# USB_Experiment_Board.net
KiCad netlist of a schematic drawn in EAGLE
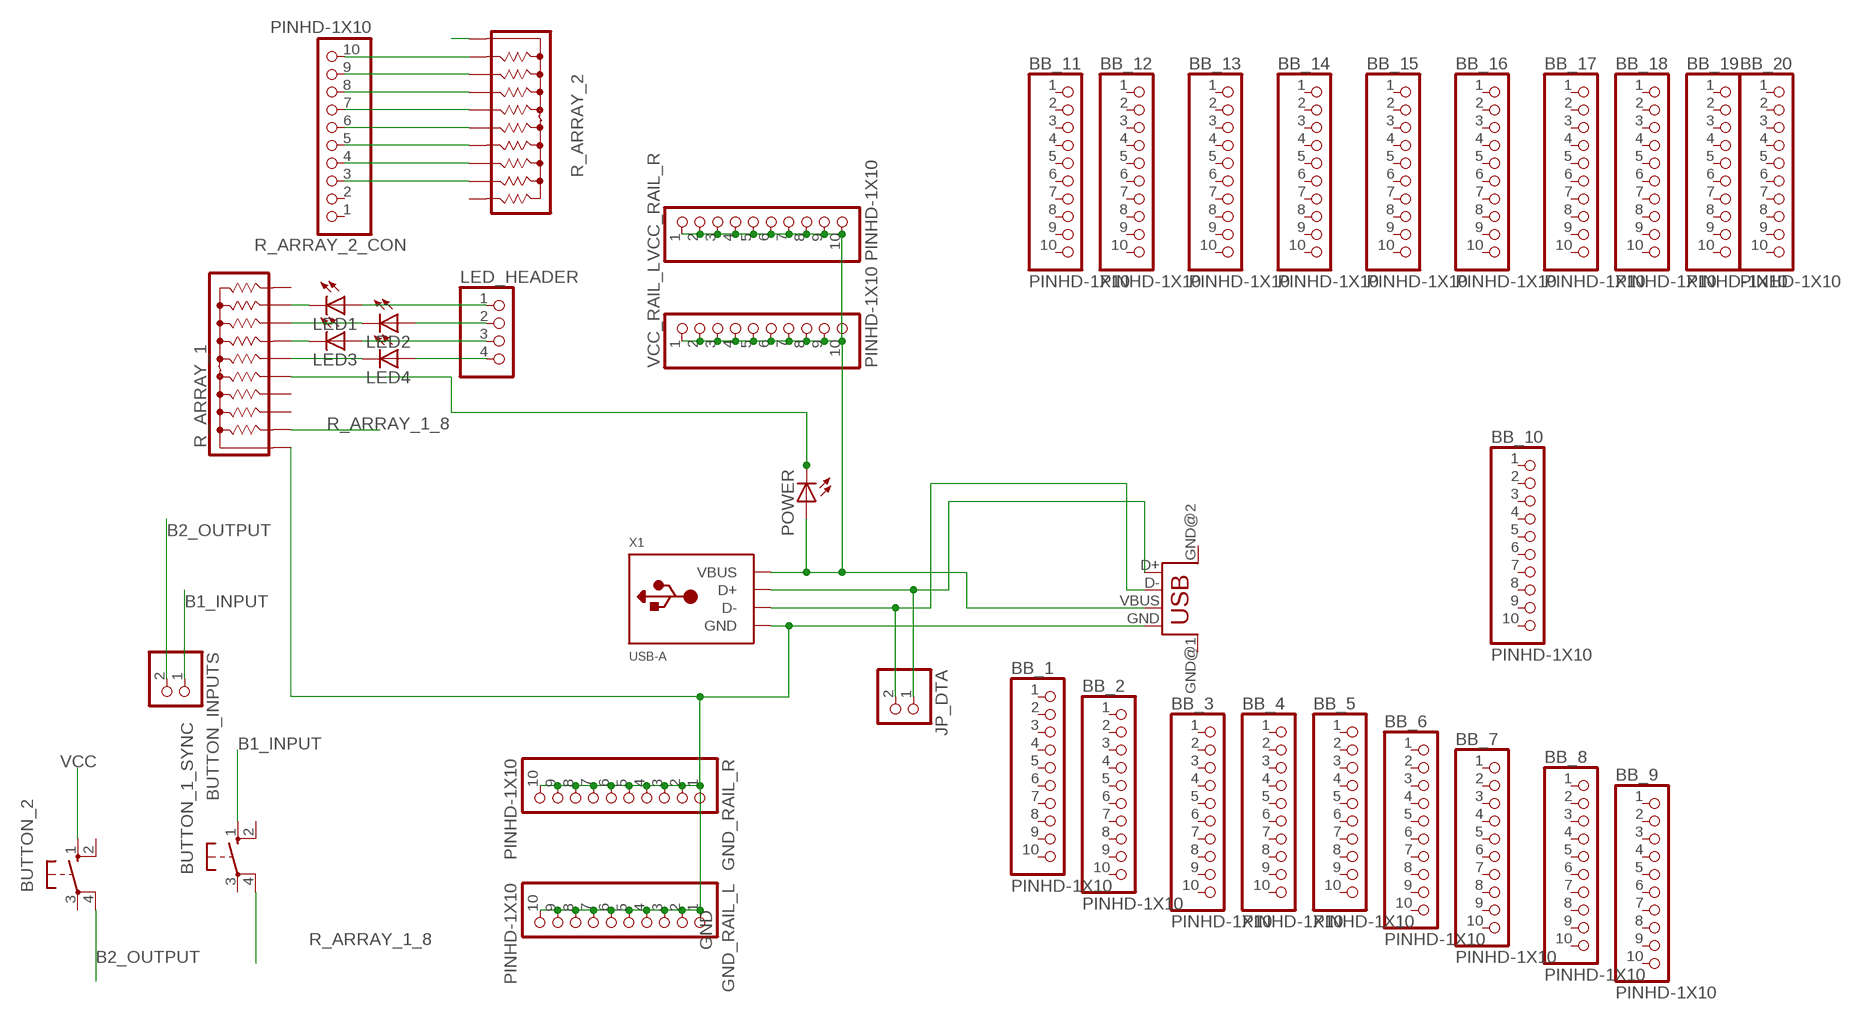
[diagram p0: schematic, sheet 1]

(export (version "E")
  (design (tool "Eeschema 10.0.6"))
  (components
    (comp (ref "BB_1")
      (value "PINHD-1X10")
      (footprint "eagle-import:1X10-BIG")
      (libsource (lib "eagle-import") (part "PINHD-1X10"))
    )
    (comp (ref "BB_2")
      (value "PINHD-1X10")
      (footprint "eagle-import:1X10-BIG")
      (libsource (lib "eagle-import") (part "PINHD-1X10"))
    )
    (comp (ref "BB_3")
      (value "PINHD-1X10")
      (footprint "eagle-import:1X10-BIG")
      (libsource (lib "eagle-import") (part "PINHD-1X10"))
    )
    (comp (ref "BB_4")
      (value "PINHD-1X10")
      (footprint "eagle-import:1X10-BIG")
      (libsource (lib "eagle-import") (part "PINHD-1X10"))
    )
    (comp (ref "BB_5")
      (value "PINHD-1X10")
      (footprint "eagle-import:1X10-BIG")
      (libsource (lib "eagle-import") (part "PINHD-1X10"))
    )
    (comp (ref "BB_6")
      (value "PINHD-1X10")
      (footprint "eagle-import:1X10-BIG")
      (libsource (lib "eagle-import") (part "PINHD-1X10"))
    )
    (comp (ref "BB_7")
      (value "PINHD-1X10")
      (footprint "eagle-import:1X10-BIG")
      (libsource (lib "eagle-import") (part "PINHD-1X10"))
    )
    (comp (ref "BB_8")
      (value "PINHD-1X10")
      (footprint "eagle-import:1X10-BIG")
      (libsource (lib "eagle-import") (part "PINHD-1X10"))
    )
    (comp (ref "BB_9")
      (value "PINHD-1X10")
      (footprint "eagle-import:1X10-BIG")
      (libsource (lib "eagle-import") (part "PINHD-1X10"))
    )
    (comp (ref "BB_10")
      (value "PINHD-1X10")
      (footprint "eagle-import:1X10-BIG")
      (libsource (lib "eagle-import") (part "PINHD-1X10"))
    )
    (comp (ref "BB_11")
      (value "PINHD-1X10")
      (footprint "eagle-import:1X10-BIG")
      (libsource (lib "eagle-import") (part "PINHD-1X10"))
    )
    (comp (ref "BB_12")
      (value "PINHD-1X10")
      (footprint "eagle-import:1X10-BIG")
      (libsource (lib "eagle-import") (part "PINHD-1X10"))
    )
    (comp (ref "BB_13")
      (value "PINHD-1X10")
      (footprint "eagle-import:1X10-BIG")
      (libsource (lib "eagle-import") (part "PINHD-1X10"))
    )
    (comp (ref "BB_14")
      (value "PINHD-1X10")
      (footprint "eagle-import:1X10-BIG")
      (libsource (lib "eagle-import") (part "PINHD-1X10"))
    )
    (comp (ref "BB_15")
      (value "PINHD-1X10")
      (footprint "eagle-import:1X10-BIG")
      (libsource (lib "eagle-import") (part "PINHD-1X10"))
    )
    (comp (ref "BB_16")
      (value "PINHD-1X10")
      (footprint "eagle-import:1X10-BIG")
      (libsource (lib "eagle-import") (part "PINHD-1X10"))
    )
    (comp (ref "BB_17")
      (value "PINHD-1X10")
      (footprint "eagle-import:1X10-BIG")
      (libsource (lib "eagle-import") (part "PINHD-1X10"))
    )
    (comp (ref "BB_18")
      (value "PINHD-1X10")
      (footprint "eagle-import:1X10-BIG")
      (libsource (lib "eagle-import") (part "PINHD-1X10"))
    )
    (comp (ref "BB_19")
      (value "PINHD-1X10")
      (footprint "eagle-import:1X10-BIG")
      (libsource (lib "eagle-import") (part "PINHD-1X10"))
    )
    (comp (ref "BB_20")
      (value "PINHD-1X10")
      (footprint "eagle-import:1X10-BIG")
      (libsource (lib "eagle-import") (part "PINHD-1X10"))
    )
    (comp (ref "BUTTON_1_SYNC")
      (value "10-XX")
      (footprint "eagle-import:B3F-10XX")
      (fields (field (name "MPN") "B3F-1000"))
      (libsource (lib "eagle-import") (part "10-XX"))
    )
    (comp (ref "BUTTON_2")
      (value "10-XX")
      (footprint "eagle-import:B3F-10XX")
      (fields (field (name "MPN") "B3F-1000"))
      (libsource (lib "eagle-import") (part "10-XX"))
    )
    (comp (ref "BUTTON_INPUTS")
      (value "PINHD-1X2")
      (footprint "eagle-import:1X02")
      (libsource (lib "eagle-import") (part "PINHD-1X2"))
    )
    (comp (ref "GND_RAIL_L")
      (value "PINHD-1X10")
      (footprint "eagle-import:1X10-BIG")
      (libsource (lib "eagle-import") (part "PINHD-1X10"))
    )
    (comp (ref "GND_RAIL_R")
      (value "PINHD-1X10")
      (footprint "eagle-import:1X10-BIG")
      (libsource (lib "eagle-import") (part "PINHD-1X10"))
    )
    (comp (ref "JP_DTA")
      (value "PINHD-1X2")
      (footprint "eagle-import:1X02")
      (libsource (lib "eagle-import") (part "PINHD-1X2"))
    )
    (comp (ref "LED1")
      (value "LEDSMT1206")
      (footprint "eagle-import:1206")
      (libsource (lib "eagle-import") (part "LEDSMT1206"))
    )
    (comp (ref "LED2")
      (value "LEDSMT1206")
      (footprint "eagle-import:1206")
      (libsource (lib "eagle-import") (part "LEDSMT1206"))
    )
    (comp (ref "LED3")
      (value "LEDSMT1206")
      (footprint "eagle-import:1206")
      (libsource (lib "eagle-import") (part "LEDSMT1206"))
    )
    (comp (ref "LED4")
      (value "LEDSMT1206")
      (footprint "eagle-import:1206")
      (libsource (lib "eagle-import") (part "LEDSMT1206"))
    )
    (comp (ref "LED_HEADER")
      (value "PINHD-1X4")
      (footprint "eagle-import:1X04")
      (libsource (lib "eagle-import") (part "PINHD-1X4"))
    )
    (comp (ref "POWER")
      (value "LEDSMT1206")
      (footprint "eagle-import:1206")
      (libsource (lib "eagle-import") (part "LEDSMT1206"))
    )
    (comp (ref "R_ARRAY_1")
      (value "4610X")
      (footprint "eagle-import:SIP10")
      (libsource (lib "eagle-import") (part "4610X"))
    )
    (comp (ref "R_ARRAY_2")
      (value "4610X")
      (footprint "eagle-import:SIP10")
      (libsource (lib "eagle-import") (part "4610X"))
    )
    (comp (ref "R_ARRAY_2_CON")
      (value "PINHD-1X10")
      (footprint "eagle-import:1X10-BIG")
      (libsource (lib "eagle-import") (part "PINHD-1X10"))
    )
    (comp (ref "U$1")
      (value "USB")
      (footprint "eagle-import:USB-FEMALE-A-PTH")
      (libsource (lib "eagle-import") (part "USB"))
    )
    (comp (ref "VCC_RAIL_L")
      (value "PINHD-1X10")
      (footprint "eagle-import:1X10-BIG")
      (libsource (lib "eagle-import") (part "PINHD-1X10"))
    )
    (comp (ref "VCC_RAIL_R")
      (value "PINHD-1X10")
      (footprint "eagle-import:1X10-BIG")
      (libsource (lib "eagle-import") (part "PINHD-1X10"))
    )
    (comp (ref "X1")
      (value "USB-A")
      (footprint "eagle-import:MOLEX_480371000")
      (libsource (lib "eagle-import") (part "USB-A"))
    )
  )
  (nets
    (net (code "1") (name "/B1_INPUT") (class "Default")
      (node (ref "BUTTON_1_SYNC") (pin "1") (pinfunction "S_1") (pintype "passive"))
      (node (ref "BUTTON_INPUTS") (pin "1") (pinfunction "1_1") (pintype "passive"))
    )
    (net (code "2") (name "/B2_OUTPUT") (class "Default")
      (node (ref "BUTTON_2") (pin "4") (pinfunction "P1_4") (pintype "passive"))
      (node (ref "BUTTON_INPUTS") (pin "2") (pinfunction "2_2") (pintype "passive"))
    )
    (net (code "3") (name "/GND") (class "Default")
      (node (ref "GND_RAIL_L") (pin "1") (pinfunction "1_1") (pintype "passive"))
      (node (ref "GND_RAIL_L") (pin "10") (pinfunction "10_10") (pintype "passive"))
      (node (ref "GND_RAIL_L") (pin "2") (pinfunction "2_2") (pintype "passive"))
      (node (ref "GND_RAIL_L") (pin "3") (pinfunction "3_3") (pintype "passive"))
      (node (ref "GND_RAIL_L") (pin "4") (pinfunction "4_4") (pintype "passive"))
      (node (ref "GND_RAIL_L") (pin "5") (pinfunction "5_5") (pintype "passive"))
      (node (ref "GND_RAIL_L") (pin "6") (pinfunction "6_6") (pintype "passive"))
      (node (ref "GND_RAIL_L") (pin "7") (pinfunction "7_7") (pintype "passive"))
      (node (ref "GND_RAIL_L") (pin "8") (pinfunction "8_8") (pintype "passive"))
      (node (ref "GND_RAIL_L") (pin "9") (pinfunction "9_9") (pintype "passive"))
      (node (ref "GND_RAIL_R") (pin "1") (pinfunction "1_1") (pintype "passive"))
      (node (ref "GND_RAIL_R") (pin "10") (pinfunction "10_10") (pintype "passive"))
      (node (ref "GND_RAIL_R") (pin "2") (pinfunction "2_2") (pintype "passive"))
      (node (ref "GND_RAIL_R") (pin "3") (pinfunction "3_3") (pintype "passive"))
      (node (ref "GND_RAIL_R") (pin "4") (pinfunction "4_4") (pintype "passive"))
      (node (ref "GND_RAIL_R") (pin "5") (pinfunction "5_5") (pintype "passive"))
      (node (ref "GND_RAIL_R") (pin "6") (pinfunction "6_6") (pintype "passive"))
      (node (ref "GND_RAIL_R") (pin "7") (pinfunction "7_7") (pintype "passive"))
      (node (ref "GND_RAIL_R") (pin "8") (pinfunction "8_8") (pintype "passive"))
      (node (ref "GND_RAIL_R") (pin "9") (pinfunction "9_9") (pintype "passive"))
      (node (ref "R_ARRAY_1") (pin "1") (pinfunction "1_1") (pintype "passive"))
      (node (ref "R_ARRAY_2") (pin "1") (pinfunction "1_1") (pintype "passive"))
      (node (ref "U$1") (pin "GND") (pinfunction "GND_GND") (pintype "bidirectional"))
      (node (ref "X1") (pin "4") (pinfunction "GND_4") (pintype "power_in"))
    )
    (net (code "4") (name "/R_ARRAY_1_8") (class "Default")
      (node (ref "BUTTON_1_SYNC") (pin "4") (pinfunction "P1_4") (pintype "passive"))
      (node (ref "R_ARRAY_1") (pin "2") (pinfunction "2_2") (pintype "passive"))
    )
    (net (code "5") (name "/VCC") (class "Default")
      (node (ref "BUTTON_2") (pin "1") (pinfunction "S_1") (pintype "passive"))
      (node (ref "POWER") (pin "A") (pinfunction "A_A") (pintype "passive"))
      (node (ref "U$1") (pin "VBUS") (pinfunction "VBUS_VBUS") (pintype "bidirectional"))
      (node (ref "VCC_RAIL_L") (pin "1") (pinfunction "1_1") (pintype "passive"))
      (node (ref "VCC_RAIL_L") (pin "10") (pinfunction "10_10") (pintype "passive"))
      (node (ref "VCC_RAIL_L") (pin "2") (pinfunction "2_2") (pintype "passive"))
      (node (ref "VCC_RAIL_L") (pin "3") (pinfunction "3_3") (pintype "passive"))
      (node (ref "VCC_RAIL_L") (pin "4") (pinfunction "4_4") (pintype "passive"))
      (node (ref "VCC_RAIL_L") (pin "5") (pinfunction "5_5") (pintype "passive"))
      (node (ref "VCC_RAIL_L") (pin "6") (pinfunction "6_6") (pintype "passive"))
      (node (ref "VCC_RAIL_L") (pin "7") (pinfunction "7_7") (pintype "passive"))
      (node (ref "VCC_RAIL_L") (pin "8") (pinfunction "8_8") (pintype "passive"))
      (node (ref "VCC_RAIL_L") (pin "9") (pinfunction "9_9") (pintype "passive"))
      (node (ref "VCC_RAIL_R") (pin "1") (pinfunction "1_1") (pintype "passive"))
      (node (ref "VCC_RAIL_R") (pin "10") (pinfunction "10_10") (pintype "passive"))
      (node (ref "VCC_RAIL_R") (pin "2") (pinfunction "2_2") (pintype "passive"))
      (node (ref "VCC_RAIL_R") (pin "3") (pinfunction "3_3") (pintype "passive"))
      (node (ref "VCC_RAIL_R") (pin "4") (pinfunction "4_4") (pintype "passive"))
      (node (ref "VCC_RAIL_R") (pin "5") (pinfunction "5_5") (pintype "passive"))
      (node (ref "VCC_RAIL_R") (pin "6") (pinfunction "6_6") (pintype "passive"))
      (node (ref "VCC_RAIL_R") (pin "7") (pinfunction "7_7") (pintype "passive"))
      (node (ref "VCC_RAIL_R") (pin "8") (pinfunction "8_8") (pintype "passive"))
      (node (ref "VCC_RAIL_R") (pin "9") (pinfunction "9_9") (pintype "passive"))
      (node (ref "X1") (pin "1") (pinfunction "VBUS_1") (pintype "power_in"))
    )
    (net (code "6") (name "Net-(LED1-PadA)") (class "Default")
      (node (ref "LED1") (pin "A") (pinfunction "A_A") (pintype "passive"))
      (node (ref "LED_HEADER") (pin "1") (pinfunction "1_1") (pintype "passive"))
    )
    (net (code "7") (name "Net-(LED1-PadC)") (class "Default")
      (node (ref "LED1") (pin "C") (pinfunction "C_C") (pintype "passive"))
      (node (ref "R_ARRAY_1") (pin "9") (pinfunction "9_9") (pintype "passive"))
    )
    (net (code "8") (name "Net-(LED2-PadA)") (class "Default")
      (node (ref "LED2") (pin "A") (pinfunction "A_A") (pintype "passive"))
      (node (ref "LED_HEADER") (pin "2") (pinfunction "2_2") (pintype "passive"))
    )
    (net (code "9") (name "Net-(LED2-PadC)") (class "Default")
      (node (ref "LED2") (pin "C") (pinfunction "C_C") (pintype "passive"))
      (node (ref "R_ARRAY_1") (pin "8") (pinfunction "8_8") (pintype "passive"))
    )
    (net (code "10") (name "Net-(LED3-PadA)") (class "Default")
      (node (ref "LED3") (pin "A") (pinfunction "A_A") (pintype "passive"))
      (node (ref "LED_HEADER") (pin "3") (pinfunction "3_3") (pintype "passive"))
    )
    (net (code "11") (name "Net-(LED3-PadC)") (class "Default")
      (node (ref "LED3") (pin "C") (pinfunction "C_C") (pintype "passive"))
      (node (ref "R_ARRAY_1") (pin "7") (pinfunction "7_7") (pintype "passive"))
    )
    (net (code "12") (name "Net-(LED4-PadA)") (class "Default")
      (node (ref "LED4") (pin "A") (pinfunction "A_A") (pintype "passive"))
      (node (ref "LED_HEADER") (pin "4") (pinfunction "4_4") (pintype "passive"))
    )
    (net (code "13") (name "Net-(LED4-PadC)") (class "Default")
      (node (ref "LED4") (pin "C") (pinfunction "C_C") (pintype "passive"))
      (node (ref "R_ARRAY_1") (pin "6") (pinfunction "6_6") (pintype "passive"))
    )
    (net (code "14") (name "Net-(POWER-PadC)") (class "Default")
      (node (ref "POWER") (pin "C") (pinfunction "C_C") (pintype "passive"))
      (node (ref "R_ARRAY_1") (pin "5") (pinfunction "5_5") (pintype "passive"))
    )
    (net (code "15") (name "Net-(R_ARRAY_2-Pad2)") (class "Default")
      (node (ref "R_ARRAY_2") (pin "2") (pinfunction "2_2") (pintype "passive"))
      (node (ref "R_ARRAY_2_CON") (pin "10") (pinfunction "10_10") (pintype "passive"))
    )
    (net (code "16") (name "Net-(R_ARRAY_2-Pad3)") (class "Default")
      (node (ref "R_ARRAY_2") (pin "3") (pinfunction "3_3") (pintype "passive"))
      (node (ref "R_ARRAY_2_CON") (pin "9") (pinfunction "9_9") (pintype "passive"))
    )
    (net (code "17") (name "Net-(R_ARRAY_2-Pad4)") (class "Default")
      (node (ref "R_ARRAY_2") (pin "4") (pinfunction "4_4") (pintype "passive"))
      (node (ref "R_ARRAY_2_CON") (pin "8") (pinfunction "8_8") (pintype "passive"))
    )
    (net (code "18") (name "Net-(R_ARRAY_2-Pad5)") (class "Default")
      (node (ref "R_ARRAY_2") (pin "5") (pinfunction "5_5") (pintype "passive"))
      (node (ref "R_ARRAY_2_CON") (pin "7") (pinfunction "7_7") (pintype "passive"))
    )
    (net (code "19") (name "Net-(R_ARRAY_2-Pad6)") (class "Default")
      (node (ref "R_ARRAY_2") (pin "6") (pinfunction "6_6") (pintype "passive"))
      (node (ref "R_ARRAY_2_CON") (pin "6") (pinfunction "6_6") (pintype "passive"))
    )
    (net (code "20") (name "Net-(R_ARRAY_2-Pad7)") (class "Default")
      (node (ref "R_ARRAY_2") (pin "7") (pinfunction "7_7") (pintype "passive"))
      (node (ref "R_ARRAY_2_CON") (pin "5") (pinfunction "5_5") (pintype "passive"))
    )
    (net (code "21") (name "Net-(R_ARRAY_2-Pad8)") (class "Default")
      (node (ref "R_ARRAY_2") (pin "8") (pinfunction "8_8") (pintype "passive"))
      (node (ref "R_ARRAY_2_CON") (pin "4") (pinfunction "4_4") (pintype "passive"))
    )
    (net (code "22") (name "Net-(R_ARRAY_2-Pad9)") (class "Default")
      (node (ref "R_ARRAY_2") (pin "9") (pinfunction "9_9") (pintype "passive"))
      (node (ref "R_ARRAY_2_CON") (pin "3") (pinfunction "3_3") (pintype "passive"))
    )
    (net (code "23") (name "Net-(X1-D+)") (class "Default")
      (node (ref "JP_DTA") (pin "1") (pinfunction "1_1") (pintype "passive"))
      (node (ref "U$1") (pin "D+") (pinfunction "D+_D+") (pintype "bidirectional"))
      (node (ref "X1") (pin "3") (pinfunction "D+_3") (pintype "bidirectional"))
    )
    (net (code "24") (name "Net-(X1-D-)") (class "Default")
      (node (ref "JP_DTA") (pin "2") (pinfunction "2_2") (pintype "passive"))
      (node (ref "U$1") (pin "D-") (pinfunction "D-_D-") (pintype "bidirectional"))
      (node (ref "X1") (pin "2") (pinfunction "D-_2") (pintype "bidirectional"))
    )
    (net (code "25") (name "unconnected-(BB_1-Pad1)") (class "Default")
      (node (ref "BB_1") (pin "1") (pinfunction "1_1") (pintype "passive"))
    )
    (net (code "26") (name "unconnected-(BB_1-Pad2)") (class "Default")
      (node (ref "BB_1") (pin "2") (pinfunction "2_2") (pintype "passive"))
    )
    (net (code "27") (name "unconnected-(BB_1-Pad3)") (class "Default")
      (node (ref "BB_1") (pin "3") (pinfunction "3_3") (pintype "passive"))
    )
    (net (code "28") (name "unconnected-(BB_1-Pad4)") (class "Default")
      (node (ref "BB_1") (pin "4") (pinfunction "4_4") (pintype "passive"))
    )
    (net (code "29") (name "unconnected-(BB_1-Pad5)") (class "Default")
      (node (ref "BB_1") (pin "5") (pinfunction "5_5") (pintype "passive"))
    )
    (net (code "30") (name "unconnected-(BB_1-Pad6)") (class "Default")
      (node (ref "BB_1") (pin "6") (pinfunction "6_6") (pintype "passive"))
    )
    (net (code "31") (name "unconnected-(BB_1-Pad7)") (class "Default")
      (node (ref "BB_1") (pin "7") (pinfunction "7_7") (pintype "passive"))
    )
    (net (code "32") (name "unconnected-(BB_1-Pad8)") (class "Default")
      (node (ref "BB_1") (pin "8") (pinfunction "8_8") (pintype "passive"))
    )
    (net (code "33") (name "unconnected-(BB_1-Pad9)") (class "Default")
      (node (ref "BB_1") (pin "9") (pinfunction "9_9") (pintype "passive"))
    )
    (net (code "34") (name "unconnected-(BB_1-Pad10)") (class "Default")
      (node (ref "BB_1") (pin "10") (pinfunction "10_10") (pintype "passive"))
    )
    (net (code "35") (name "unconnected-(BB_2-Pad1)") (class "Default")
      (node (ref "BB_2") (pin "1") (pinfunction "1_1") (pintype "passive"))
    )
    (net (code "36") (name "unconnected-(BB_2-Pad2)") (class "Default")
      (node (ref "BB_2") (pin "2") (pinfunction "2_2") (pintype "passive"))
    )
    (net (code "37") (name "unconnected-(BB_2-Pad3)") (class "Default")
      (node (ref "BB_2") (pin "3") (pinfunction "3_3") (pintype "passive"))
    )
    (net (code "38") (name "unconnected-(BB_2-Pad4)") (class "Default")
      (node (ref "BB_2") (pin "4") (pinfunction "4_4") (pintype "passive"))
    )
    (net (code "39") (name "unconnected-(BB_2-Pad5)") (class "Default")
      (node (ref "BB_2") (pin "5") (pinfunction "5_5") (pintype "passive"))
    )
    (net (code "40") (name "unconnected-(BB_2-Pad6)") (class "Default")
      (node (ref "BB_2") (pin "6") (pinfunction "6_6") (pintype "passive"))
    )
    (net (code "41") (name "unconnected-(BB_2-Pad7)") (class "Default")
      (node (ref "BB_2") (pin "7") (pinfunction "7_7") (pintype "passive"))
    )
    (net (code "42") (name "unconnected-(BB_2-Pad8)") (class "Default")
      (node (ref "BB_2") (pin "8") (pinfunction "8_8") (pintype "passive"))
    )
    (net (code "43") (name "unconnected-(BB_2-Pad9)") (class "Default")
      (node (ref "BB_2") (pin "9") (pinfunction "9_9") (pintype "passive"))
    )
    (net (code "44") (name "unconnected-(BB_2-Pad10)") (class "Default")
      (node (ref "BB_2") (pin "10") (pinfunction "10_10") (pintype "passive"))
    )
    (net (code "45") (name "unconnected-(BB_3-Pad1)") (class "Default")
      (node (ref "BB_3") (pin "1") (pinfunction "1_1") (pintype "passive"))
    )
    (net (code "46") (name "unconnected-(BB_3-Pad2)") (class "Default")
      (node (ref "BB_3") (pin "2") (pinfunction "2_2") (pintype "passive"))
    )
    (net (code "47") (name "unconnected-(BB_3-Pad3)") (class "Default")
      (node (ref "BB_3") (pin "3") (pinfunction "3_3") (pintype "passive"))
    )
    (net (code "48") (name "unconnected-(BB_3-Pad4)") (class "Default")
      (node (ref "BB_3") (pin "4") (pinfunction "4_4") (pintype "passive"))
    )
    (net (code "49") (name "unconnected-(BB_3-Pad5)") (class "Default")
      (node (ref "BB_3") (pin "5") (pinfunction "5_5") (pintype "passive"))
    )
    (net (code "50") (name "unconnected-(BB_3-Pad6)") (class "Default")
      (node (ref "BB_3") (pin "6") (pinfunction "6_6") (pintype "passive"))
    )
    (net (code "51") (name "unconnected-(BB_3-Pad7)") (class "Default")
      (node (ref "BB_3") (pin "7") (pinfunction "7_7") (pintype "passive"))
    )
    (net (code "52") (name "unconnected-(BB_3-Pad8)") (class "Default")
      (node (ref "BB_3") (pin "8") (pinfunction "8_8") (pintype "passive"))
    )
    (net (code "53") (name "unconnected-(BB_3-Pad9)") (class "Default")
      (node (ref "BB_3") (pin "9") (pinfunction "9_9") (pintype "passive"))
    )
    (net (code "54") (name "unconnected-(BB_3-Pad10)") (class "Default")
      (node (ref "BB_3") (pin "10") (pinfunction "10_10") (pintype "passive"))
    )
    (net (code "55") (name "unconnected-(BB_4-Pad1)") (class "Default")
      (node (ref "BB_4") (pin "1") (pinfunction "1_1") (pintype "passive"))
    )
    (net (code "56") (name "unconnected-(BB_4-Pad2)") (class "Default")
      (node (ref "BB_4") (pin "2") (pinfunction "2_2") (pintype "passive"))
    )
    (net (code "57") (name "unconnected-(BB_4-Pad3)") (class "Default")
      (node (ref "BB_4") (pin "3") (pinfunction "3_3") (pintype "passive"))
    )
    (net (code "58") (name "unconnected-(BB_4-Pad4)") (class "Default")
      (node (ref "BB_4") (pin "4") (pinfunction "4_4") (pintype "passive"))
    )
    (net (code "59") (name "unconnected-(BB_4-Pad5)") (class "Default")
      (node (ref "BB_4") (pin "5") (pinfunction "5_5") (pintype "passive"))
    )
    (net (code "60") (name "unconnected-(BB_4-Pad6)") (class "Default")
      (node (ref "BB_4") (pin "6") (pinfunction "6_6") (pintype "passive"))
    )
    (net (code "61") (name "unconnected-(BB_4-Pad7)") (class "Default")
      (node (ref "BB_4") (pin "7") (pinfunction "7_7") (pintype "passive"))
    )
    (net (code "62") (name "unconnected-(BB_4-Pad8)") (class "Default")
      (node (ref "BB_4") (pin "8") (pinfunction "8_8") (pintype "passive"))
    )
    (net (code "63") (name "unconnected-(BB_4-Pad9)") (class "Default")
      (node (ref "BB_4") (pin "9") (pinfunction "9_9") (pintype "passive"))
    )
    (net (code "64") (name "unconnected-(BB_4-Pad10)") (class "Default")
      (node (ref "BB_4") (pin "10") (pinfunction "10_10") (pintype "passive"))
    )
    (net (code "65") (name "unconnected-(BB_5-Pad1)") (class "Default")
      (node (ref "BB_5") (pin "1") (pinfunction "1_1") (pintype "passive"))
    )
    (net (code "66") (name "unconnected-(BB_5-Pad2)") (class "Default")
      (node (ref "BB_5") (pin "2") (pinfunction "2_2") (pintype "passive"))
    )
    (net (code "67") (name "unconnected-(BB_5-Pad3)") (class "Default")
      (node (ref "BB_5") (pin "3") (pinfunction "3_3") (pintype "passive"))
    )
    (net (code "68") (name "unconnected-(BB_5-Pad4)") (class "Default")
      (node (ref "BB_5") (pin "4") (pinfunction "4_4") (pintype "passive"))
    )
    (net (code "69") (name "unconnected-(BB_5-Pad5)") (class "Default")
      (node (ref "BB_5") (pin "5") (pinfunction "5_5") (pintype "passive"))
    )
    (net (code "70") (name "unconnected-(BB_5-Pad6)") (class "Default")
      (node (ref "BB_5") (pin "6") (pinfunction "6_6") (pintype "passive"))
    )
    (net (code "71") (name "unconnected-(BB_5-Pad7)") (class "Default")
      (node (ref "BB_5") (pin "7") (pinfunction "7_7") (pintype "passive"))
    )
    (net (code "72") (name "unconnected-(BB_5-Pad8)") (class "Default")
      (node (ref "BB_5") (pin "8") (pinfunction "8_8") (pintype "passive"))
    )
    (net (code "73") (name "unconnected-(BB_5-Pad9)") (class "Default")
      (node (ref "BB_5") (pin "9") (pinfunction "9_9") (pintype "passive"))
    )
    (net (code "74") (name "unconnected-(BB_5-Pad10)") (class "Default")
      (node (ref "BB_5") (pin "10") (pinfunction "10_10") (pintype "passive"))
    )
    (net (code "75") (name "unconnected-(BB_6-Pad1)") (class "Default")
      (node (ref "BB_6") (pin "1") (pinfunction "1_1") (pintype "passive"))
    )
    (net (code "76") (name "unconnected-(BB_6-Pad2)") (class "Default")
      (node (ref "BB_6") (pin "2") (pinfunction "2_2") (pintype "passive"))
    )
    (net (code "77") (name "unconnected-(BB_6-Pad3)") (class "Default")
      (node (ref "BB_6") (pin "3") (pinfunction "3_3") (pintype "passive"))
    )
    (net (code "78") (name "unconnected-(BB_6-Pad4)") (class "Default")
      (node (ref "BB_6") (pin "4") (pinfunction "4_4") (pintype "passive"))
    )
    (net (code "79") (name "unconnected-(BB_6-Pad5)") (class "Default")
      (node (ref "BB_6") (pin "5") (pinfunction "5_5") (pintype "passive"))
    )
    (net (code "80") (name "unconnected-(BB_6-Pad6)") (class "Default")
      (node (ref "BB_6") (pin "6") (pinfunction "6_6") (pintype "passive"))
    )
    (net (code "81") (name "unconnected-(BB_6-Pad7)") (class "Default")
      (node (ref "BB_6") (pin "7") (pinfunction "7_7") (pintype "passive"))
    )
    (net (code "82") (name "unconnected-(BB_6-Pad8)") (class "Default")
      (node (ref "BB_6") (pin "8") (pinfunction "8_8") (pintype "passive"))
    )
    (net (code "83") (name "unconnected-(BB_6-Pad9)") (class "Default")
      (node (ref "BB_6") (pin "9") (pinfunction "9_9") (pintype "passive"))
    )
    (net (code "84") (name "unconnected-(BB_6-Pad10)") (class "Default")
      (node (ref "BB_6") (pin "10") (pinfunction "10_10") (pintype "passive"))
    )
    (net (code "85") (name "unconnected-(BB_7-Pad1)") (class "Default")
      (node (ref "BB_7") (pin "1") (pinfunction "1_1") (pintype "passive"))
    )
    (net (code "86") (name "unconnected-(BB_7-Pad2)") (class "Default")
      (node (ref "BB_7") (pin "2") (pinfunction "2_2") (pintype "passive"))
    )
    (net (code "87") (name "unconnected-(BB_7-Pad3)") (class "Default")
      (node (ref "BB_7") (pin "3") (pinfunction "3_3") (pintype "passive"))
    )
    (net (code "88") (name "unconnected-(BB_7-Pad4)") (class "Default")
      (node (ref "BB_7") (pin "4") (pinfunction "4_4") (pintype "passive"))
    )
    (net (code "89") (name "unconnected-(BB_7-Pad5)") (class "Default")
      (node (ref "BB_7") (pin "5") (pinfunction "5_5") (pintype "passive"))
    )
    (net (code "90") (name "unconnected-(BB_7-Pad6)") (class "Default")
      (node (ref "BB_7") (pin "6") (pinfunction "6_6") (pintype "passive"))
    )
    (net (code "91") (name "unconnected-(BB_7-Pad7)") (class "Default")
      (node (ref "BB_7") (pin "7") (pinfunction "7_7") (pintype "passive"))
    )
    (net (code "92") (name "unconnected-(BB_7-Pad8)") (class "Default")
      (node (ref "BB_7") (pin "8") (pinfunction "8_8") (pintype "passive"))
    )
    (net (code "93") (name "unconnected-(BB_7-Pad9)") (class "Default")
      (node (ref "BB_7") (pin "9") (pinfunction "9_9") (pintype "passive"))
    )
    (net (code "94") (name "unconnected-(BB_7-Pad10)") (class "Default")
      (node (ref "BB_7") (pin "10") (pinfunction "10_10") (pintype "passive"))
    )
    (net (code "95") (name "unconnected-(BB_8-Pad1)") (class "Default")
      (node (ref "BB_8") (pin "1") (pinfunction "1_1") (pintype "passive"))
    )
    (net (code "96") (name "unconnected-(BB_8-Pad2)") (class "Default")
      (node (ref "BB_8") (pin "2") (pinfunction "2_2") (pintype "passive"))
    )
    (net (code "97") (name "unconnected-(BB_8-Pad3)") (class "Default")
      (node (ref "BB_8") (pin "3") (pinfunction "3_3") (pintype "passive"))
    )
    (net (code "98") (name "unconnected-(BB_8-Pad4)") (class "Default")
      (node (ref "BB_8") (pin "4") (pinfunction "4_4") (pintype "passive"))
    )
    (net (code "99") (name "unconnected-(BB_8-Pad5)") (class "Default")
      (node (ref "BB_8") (pin "5") (pinfunction "5_5") (pintype "passive"))
    )
    (net (code "100") (name "unconnected-(BB_8-Pad6)") (class "Default")
      (node (ref "BB_8") (pin "6") (pinfunction "6_6") (pintype "passive"))
    )
    (net (code "101") (name "unconnected-(BB_8-Pad7)") (class "Default")
      (node (ref "BB_8") (pin "7") (pinfunction "7_7") (pintype "passive"))
    )
    (net (code "102") (name "unconnected-(BB_8-Pad8)") (class "Default")
      (node (ref "BB_8") (pin "8") (pinfunction "8_8") (pintype "passive"))
    )
    (net (code "103") (name "unconnected-(BB_8-Pad9)") (class "Default")
      (node (ref "BB_8") (pin "9") (pinfunction "9_9") (pintype "passive"))
    )
    (net (code "104") (name "unconnected-(BB_8-Pad10)") (class "Default")
      (node (ref "BB_8") (pin "10") (pinfunction "10_10") (pintype "passive"))
    )
    (net (code "105") (name "unconnected-(BB_9-Pad1)") (class "Default")
      (node (ref "BB_9") (pin "1") (pinfunction "1_1") (pintype "passive"))
    )
    (net (code "106") (name "unconnected-(BB_9-Pad2)") (class "Default")
      (node (ref "BB_9") (pin "2") (pinfunction "2_2") (pintype "passive"))
    )
    (net (code "107") (name "unconnected-(BB_9-Pad3)") (class "Default")
      (node (ref "BB_9") (pin "3") (pinfunction "3_3") (pintype "passive"))
    )
    (net (code "108") (name "unconnected-(BB_9-Pad4)") (class "Default")
      (node (ref "BB_9") (pin "4") (pinfunction "4_4") (pintype "passive"))
    )
    (net (code "109") (name "unconnected-(BB_9-Pad5)") (class "Default")
      (node (ref "BB_9") (pin "5") (pinfunction "5_5") (pintype "passive"))
    )
    (net (code "110") (name "unconnected-(BB_9-Pad6)") (class "Default")
      (node (ref "BB_9") (pin "6") (pinfunction "6_6") (pintype "passive"))
    )
    (net (code "111") (name "unconnected-(BB_9-Pad7)") (class "Default")
      (node (ref "BB_9") (pin "7") (pinfunction "7_7") (pintype "passive"))
    )
    (net (code "112") (name "unconnected-(BB_9-Pad8)") (class "Default")
      (node (ref "BB_9") (pin "8") (pinfunction "8_8") (pintype "passive"))
    )
    (net (code "113") (name "unconnected-(BB_9-Pad9)") (class "Default")
      (node (ref "BB_9") (pin "9") (pinfunction "9_9") (pintype "passive"))
    )
    (net (code "114") (name "unconnected-(BB_9-Pad10)") (class "Default")
      (node (ref "BB_9") (pin "10") (pinfunction "10_10") (pintype "passive"))
    )
    (net (code "115") (name "unconnected-(BB_10-Pad1)") (class "Default")
      (node (ref "BB_10") (pin "1") (pinfunction "1_1") (pintype "passive"))
    )
    (net (code "116") (name "unconnected-(BB_10-Pad2)") (class "Default")
      (node (ref "BB_10") (pin "2") (pinfunction "2_2") (pintype "passive"))
    )
    (net (code "117") (name "unconnected-(BB_10-Pad3)") (class "Default")
      (node (ref "BB_10") (pin "3") (pinfunction "3_3") (pintype "passive"))
    )
    (net (code "118") (name "unconnected-(BB_10-Pad4)") (class "Default")
      (node (ref "BB_10") (pin "4") (pinfunction "4_4") (pintype "passive"))
    )
    (net (code "119") (name "unconnected-(BB_10-Pad5)") (class "Default")
      (node (ref "BB_10") (pin "5") (pinfunction "5_5") (pintype "passive"))
    )
    (net (code "120") (name "unconnected-(BB_10-Pad6)") (class "Default")
      (node (ref "BB_10") (pin "6") (pinfunction "6_6") (pintype "passive"))
    )
    (net (code "121") (name "unconnected-(BB_10-Pad7)") (class "Default")
      (node (ref "BB_10") (pin "7") (pinfunction "7_7") (pintype "passive"))
    )
    (net (code "122") (name "unconnected-(BB_10-Pad8)") (class "Default")
      (node (ref "BB_10") (pin "8") (pinfunction "8_8") (pintype "passive"))
    )
    (net (code "123") (name "unconnected-(BB_10-Pad9)") (class "Default")
      (node (ref "BB_10") (pin "9") (pinfunction "9_9") (pintype "passive"))
    )
    (net (code "124") (name "unconnected-(BB_10-Pad10)") (class "Default")
      (node (ref "BB_10") (pin "10") (pinfunction "10_10") (pintype "passive"))
    )
    (net (code "125") (name "unconnected-(BB_11-Pad1)") (class "Default")
      (node (ref "BB_11") (pin "1") (pinfunction "1_1") (pintype "passive"))
    )
    (net (code "126") (name "unconnected-(BB_11-Pad2)") (class "Default")
      (node (ref "BB_11") (pin "2") (pinfunction "2_2") (pintype "passive"))
    )
    (net (code "127") (name "unconnected-(BB_11-Pad3)") (class "Default")
      (node (ref "BB_11") (pin "3") (pinfunction "3_3") (pintype "passive"))
    )
    (net (code "128") (name "unconnected-(BB_11-Pad4)") (class "Default")
      (node (ref "BB_11") (pin "4") (pinfunction "4_4") (pintype "passive"))
    )
    (net (code "129") (name "unconnected-(BB_11-Pad5)") (class "Default")
      (node (ref "BB_11") (pin "5") (pinfunction "5_5") (pintype "passive"))
    )
    (net (code "130") (name "unconnected-(BB_11-Pad6)") (class "Default")
      (node (ref "BB_11") (pin "6") (pinfunction "6_6") (pintype "passive"))
    )
    (net (code "131") (name "unconnected-(BB_11-Pad7)") (class "Default")
      (node (ref "BB_11") (pin "7") (pinfunction "7_7") (pintype "passive"))
    )
    (net (code "132") (name "unconnected-(BB_11-Pad8)") (class "Default")
      (node (ref "BB_11") (pin "8") (pinfunction "8_8") (pintype "passive"))
    )
    (net (code "133") (name "unconnected-(BB_11-Pad9)") (class "Default")
      (node (ref "BB_11") (pin "9") (pinfunction "9_9") (pintype "passive"))
    )
    (net (code "134") (name "unconnected-(BB_11-Pad10)") (class "Default")
      (node (ref "BB_11") (pin "10") (pinfunction "10_10") (pintype "passive"))
    )
    (net (code "135") (name "unconnected-(BB_12-Pad1)") (class "Default")
      (node (ref "BB_12") (pin "1") (pinfunction "1_1") (pintype "passive"))
    )
    (net (code "136") (name "unconnected-(BB_12-Pad2)") (class "Default")
      (node (ref "BB_12") (pin "2") (pinfunction "2_2") (pintype "passive"))
    )
    (net (code "137") (name "unconnected-(BB_12-Pad3)") (class "Default")
      (node (ref "BB_12") (pin "3") (pinfunction "3_3") (pintype "passive"))
    )
    (net (code "138") (name "unconnected-(BB_12-Pad4)") (class "Default")
      (node (ref "BB_12") (pin "4") (pinfunction "4_4") (pintype "passive"))
    )
    (net (code "139") (name "unconnected-(BB_12-Pad5)") (class "Default")
      (node (ref "BB_12") (pin "5") (pinfunction "5_5") (pintype "passive"))
    )
    (net (code "140") (name "unconnected-(BB_12-Pad6)") (class "Default")
      (node (ref "BB_12") (pin "6") (pinfunction "6_6") (pintype "passive"))
    )
    (net (code "141") (name "unconnected-(BB_12-Pad7)") (class "Default")
      (node (ref "BB_12") (pin "7") (pinfunction "7_7") (pintype "passive"))
    )
    (net (code "142") (name "unconnected-(BB_12-Pad8)") (class "Default")
      (node (ref "BB_12") (pin "8") (pinfunction "8_8") (pintype "passive"))
    )
    (net (code "143") (name "unconnected-(BB_12-Pad9)") (class "Default")
      (node (ref "BB_12") (pin "9") (pinfunction "9_9") (pintype "passive"))
    )
    (net (code "144") (name "unconnected-(BB_12-Pad10)") (class "Default")
      (node (ref "BB_12") (pin "10") (pinfunction "10_10") (pintype "passive"))
    )
    (net (code "145") (name "unconnected-(BB_13-Pad1)") (class "Default")
      (node (ref "BB_13") (pin "1") (pinfunction "1_1") (pintype "passive"))
    )
    (net (code "146") (name "unconnected-(BB_13-Pad2)") (class "Default")
      (node (ref "BB_13") (pin "2") (pinfunction "2_2") (pintype "passive"))
    )
    (net (code "147") (name "unconnected-(BB_13-Pad3)") (class "Default")
      (node (ref "BB_13") (pin "3") (pinfunction "3_3") (pintype "passive"))
    )
    (net (code "148") (name "unconnected-(BB_13-Pad4)") (class "Default")
      (node (ref "BB_13") (pin "4") (pinfunction "4_4") (pintype "passive"))
    )
    (net (code "149") (name "unconnected-(BB_13-Pad5)") (class "Default")
      (node (ref "BB_13") (pin "5") (pinfunction "5_5") (pintype "passive"))
    )
    (net (code "150") (name "unconnected-(BB_13-Pad6)") (class "Default")
      (node (ref "BB_13") (pin "6") (pinfunction "6_6") (pintype "passive"))
    )
    (net (code "151") (name "unconnected-(BB_13-Pad7)") (class "Default")
      (node (ref "BB_13") (pin "7") (pinfunction "7_7") (pintype "passive"))
    )
    (net (code "152") (name "unconnected-(BB_13-Pad8)") (class "Default")
      (node (ref "BB_13") (pin "8") (pinfunction "8_8") (pintype "passive"))
    )
    (net (code "153") (name "unconnected-(BB_13-Pad9)") (class "Default")
      (node (ref "BB_13") (pin "9") (pinfunction "9_9") (pintype "passive"))
    )
    (net (code "154") (name "unconnected-(BB_13-Pad10)") (class "Default")
      (node (ref "BB_13") (pin "10") (pinfunction "10_10") (pintype "passive"))
    )
    (net (code "155") (name "unconnected-(BB_14-Pad1)") (class "Default")
      (node (ref "BB_14") (pin "1") (pinfunction "1_1") (pintype "passive"))
    )
    (net (code "156") (name "unconnected-(BB_14-Pad2)") (class "Default")
      (node (ref "BB_14") (pin "2") (pinfunction "2_2") (pintype "passive"))
    )
    (net (code "157") (name "unconnected-(BB_14-Pad3)") (class "Default")
      (node (ref "BB_14") (pin "3") (pinfunction "3_3") (pintype "passive"))
    )
    (net (code "158") (name "unconnected-(BB_14-Pad4)") (class "Default")
      (node (ref "BB_14") (pin "4") (pinfunction "4_4") (pintype "passive"))
    )
    (net (code "159") (name "unconnected-(BB_14-Pad5)") (class "Default")
      (node (ref "BB_14") (pin "5") (pinfunction "5_5") (pintype "passive"))
    )
    (net (code "160") (name "unconnected-(BB_14-Pad6)") (class "Default")
      (node (ref "BB_14") (pin "6") (pinfunction "6_6") (pintype "passive"))
    )
    (net (code "161") (name "unconnected-(BB_14-Pad7)") (class "Default")
      (node (ref "BB_14") (pin "7") (pinfunction "7_7") (pintype "passive"))
    )
    (net (code "162") (name "unconnected-(BB_14-Pad8)") (class "Default")
      (node (ref "BB_14") (pin "8") (pinfunction "8_8") (pintype "passive"))
    )
    (net (code "163") (name "unconnected-(BB_14-Pad9)") (class "Default")
      (node (ref "BB_14") (pin "9") (pinfunction "9_9") (pintype "passive"))
    )
    (net (code "164") (name "unconnected-(BB_14-Pad10)") (class "Default")
      (node (ref "BB_14") (pin "10") (pinfunction "10_10") (pintype "passive"))
    )
    (net (code "165") (name "unconnected-(BB_15-Pad1)") (class "Default")
      (node (ref "BB_15") (pin "1") (pinfunction "1_1") (pintype "passive"))
    )
    (net (code "166") (name "unconnected-(BB_15-Pad2)") (class "Default")
      (node (ref "BB_15") (pin "2") (pinfunction "2_2") (pintype "passive"))
    )
    (net (code "167") (name "unconnected-(BB_15-Pad3)") (class "Default")
      (node (ref "BB_15") (pin "3") (pinfunction "3_3") (pintype "passive"))
    )
    (net (code "168") (name "unconnected-(BB_15-Pad4)") (class "Default")
      (node (ref "BB_15") (pin "4") (pinfunction "4_4") (pintype "passive"))
    )
    (net (code "169") (name "unconnected-(BB_15-Pad5)") (class "Default")
      (node (ref "BB_15") (pin "5") (pinfunction "5_5") (pintype "passive"))
    )
    (net (code "170") (name "unconnected-(BB_15-Pad6)") (class "Default")
      (node (ref "BB_15") (pin "6") (pinfunction "6_6") (pintype "passive"))
    )
    (net (code "171") (name "unconnected-(BB_15-Pad7)") (class "Default")
      (node (ref "BB_15") (pin "7") (pinfunction "7_7") (pintype "passive"))
    )
    (net (code "172") (name "unconnected-(BB_15-Pad8)") (class "Default")
      (node (ref "BB_15") (pin "8") (pinfunction "8_8") (pintype "passive"))
    )
    (net (code "173") (name "unconnected-(BB_15-Pad9)") (class "Default")
      (node (ref "BB_15") (pin "9") (pinfunction "9_9") (pintype "passive"))
    )
    (net (code "174") (name "unconnected-(BB_15-Pad10)") (class "Default")
      (node (ref "BB_15") (pin "10") (pinfunction "10_10") (pintype "passive"))
    )
    (net (code "175") (name "unconnected-(BB_16-Pad1)") (class "Default")
      (node (ref "BB_16") (pin "1") (pinfunction "1_1") (pintype "passive"))
    )
    (net (code "176") (name "unconnected-(BB_16-Pad2)") (class "Default")
      (node (ref "BB_16") (pin "2") (pinfunction "2_2") (pintype "passive"))
    )
    (net (code "177") (name "unconnected-(BB_16-Pad3)") (class "Default")
      (node (ref "BB_16") (pin "3") (pinfunction "3_3") (pintype "passive"))
    )
    (net (code "178") (name "unconnected-(BB_16-Pad4)") (class "Default")
      (node (ref "BB_16") (pin "4") (pinfunction "4_4") (pintype "passive"))
    )
    (net (code "179") (name "unconnected-(BB_16-Pad5)") (class "Default")
      (node (ref "BB_16") (pin "5") (pinfunction "5_5") (pintype "passive"))
    )
    (net (code "180") (name "unconnected-(BB_16-Pad6)") (class "Default")
      (node (ref "BB_16") (pin "6") (pinfunction "6_6") (pintype "passive"))
    )
    (net (code "181") (name "unconnected-(BB_16-Pad7)") (class "Default")
      (node (ref "BB_16") (pin "7") (pinfunction "7_7") (pintype "passive"))
    )
    (net (code "182") (name "unconnected-(BB_16-Pad8)") (class "Default")
      (node (ref "BB_16") (pin "8") (pinfunction "8_8") (pintype "passive"))
    )
    (net (code "183") (name "unconnected-(BB_16-Pad9)") (class "Default")
      (node (ref "BB_16") (pin "9") (pinfunction "9_9") (pintype "passive"))
    )
    (net (code "184") (name "unconnected-(BB_16-Pad10)") (class "Default")
      (node (ref "BB_16") (pin "10") (pinfunction "10_10") (pintype "passive"))
    )
    (net (code "185") (name "unconnected-(BB_17-Pad1)") (class "Default")
      (node (ref "BB_17") (pin "1") (pinfunction "1_1") (pintype "passive"))
    )
    (net (code "186") (name "unconnected-(BB_17-Pad2)") (class "Default")
      (node (ref "BB_17") (pin "2") (pinfunction "2_2") (pintype "passive"))
    )
    (net (code "187") (name "unconnected-(BB_17-Pad3)") (class "Default")
      (node (ref "BB_17") (pin "3") (pinfunction "3_3") (pintype "passive"))
    )
    (net (code "188") (name "unconnected-(BB_17-Pad4)") (class "Default")
      (node (ref "BB_17") (pin "4") (pinfunction "4_4") (pintype "passive"))
    )
    (net (code "189") (name "unconnected-(BB_17-Pad5)") (class "Default")
      (node (ref "BB_17") (pin "5") (pinfunction "5_5") (pintype "passive"))
    )
    (net (code "190") (name "unconnected-(BB_17-Pad6)") (class "Default")
      (node (ref "BB_17") (pin "6") (pinfunction "6_6") (pintype "passive"))
    )
    (net (code "191") (name "unconnected-(BB_17-Pad7)") (class "Default")
      (node (ref "BB_17") (pin "7") (pinfunction "7_7") (pintype "passive"))
    )
    (net (code "192") (name "unconnected-(BB_17-Pad8)") (class "Default")
      (node (ref "BB_17") (pin "8") (pinfunction "8_8") (pintype "passive"))
    )
    (net (code "193") (name "unconnected-(BB_17-Pad9)") (class "Default")
      (node (ref "BB_17") (pin "9") (pinfunction "9_9") (pintype "passive"))
    )
    (net (code "194") (name "unconnected-(BB_17-Pad10)") (class "Default")
      (node (ref "BB_17") (pin "10") (pinfunction "10_10") (pintype "passive"))
    )
    (net (code "195") (name "unconnected-(BB_18-Pad1)") (class "Default")
      (node (ref "BB_18") (pin "1") (pinfunction "1_1") (pintype "passive"))
    )
    (net (code "196") (name "unconnected-(BB_18-Pad2)") (class "Default")
      (node (ref "BB_18") (pin "2") (pinfunction "2_2") (pintype "passive"))
    )
    (net (code "197") (name "unconnected-(BB_18-Pad3)") (class "Default")
      (node (ref "BB_18") (pin "3") (pinfunction "3_3") (pintype "passive"))
    )
    (net (code "198") (name "unconnected-(BB_18-Pad4)") (class "Default")
      (node (ref "BB_18") (pin "4") (pinfunction "4_4") (pintype "passive"))
    )
    (net (code "199") (name "unconnected-(BB_18-Pad5)") (class "Default")
      (node (ref "BB_18") (pin "5") (pinfunction "5_5") (pintype "passive"))
    )
    (net (code "200") (name "unconnected-(BB_18-Pad6)") (class "Default")
      (node (ref "BB_18") (pin "6") (pinfunction "6_6") (pintype "passive"))
    )
    (net (code "201") (name "unconnected-(BB_18-Pad7)") (class "Default")
      (node (ref "BB_18") (pin "7") (pinfunction "7_7") (pintype "passive"))
    )
    (net (code "202") (name "unconnected-(BB_18-Pad8)") (class "Default")
      (node (ref "BB_18") (pin "8") (pinfunction "8_8") (pintype "passive"))
    )
    (net (code "203") (name "unconnected-(BB_18-Pad9)") (class "Default")
      (node (ref "BB_18") (pin "9") (pinfunction "9_9") (pintype "passive"))
    )
    (net (code "204") (name "unconnected-(BB_18-Pad10)") (class "Default")
      (node (ref "BB_18") (pin "10") (pinfunction "10_10") (pintype "passive"))
    )
    (net (code "205") (name "unconnected-(BB_19-Pad1)") (class "Default")
      (node (ref "BB_19") (pin "1") (pinfunction "1_1") (pintype "passive"))
    )
    (net (code "206") (name "unconnected-(BB_19-Pad2)") (class "Default")
      (node (ref "BB_19") (pin "2") (pinfunction "2_2") (pintype "passive"))
    )
    (net (code "207") (name "unconnected-(BB_19-Pad3)") (class "Default")
      (node (ref "BB_19") (pin "3") (pinfunction "3_3") (pintype "passive"))
    )
    (net (code "208") (name "unconnected-(BB_19-Pad4)") (class "Default")
      (node (ref "BB_19") (pin "4") (pinfunction "4_4") (pintype "passive"))
    )
    (net (code "209") (name "unconnected-(BB_19-Pad5)") (class "Default")
      (node (ref "BB_19") (pin "5") (pinfunction "5_5") (pintype "passive"))
    )
    (net (code "210") (name "unconnected-(BB_19-Pad6)") (class "Default")
      (node (ref "BB_19") (pin "6") (pinfunction "6_6") (pintype "passive"))
    )
    (net (code "211") (name "unconnected-(BB_19-Pad7)") (class "Default")
      (node (ref "BB_19") (pin "7") (pinfunction "7_7") (pintype "passive"))
    )
    (net (code "212") (name "unconnected-(BB_19-Pad8)") (class "Default")
      (node (ref "BB_19") (pin "8") (pinfunction "8_8") (pintype "passive"))
    )
    (net (code "213") (name "unconnected-(BB_19-Pad9)") (class "Default")
      (node (ref "BB_19") (pin "9") (pinfunction "9_9") (pintype "passive"))
    )
    (net (code "214") (name "unconnected-(BB_19-Pad10)") (class "Default")
      (node (ref "BB_19") (pin "10") (pinfunction "10_10") (pintype "passive"))
    )
    (net (code "215") (name "unconnected-(BB_20-Pad1)") (class "Default")
      (node (ref "BB_20") (pin "1") (pinfunction "1_1") (pintype "passive"))
    )
    (net (code "216") (name "unconnected-(BB_20-Pad2)") (class "Default")
      (node (ref "BB_20") (pin "2") (pinfunction "2_2") (pintype "passive"))
    )
    (net (code "217") (name "unconnected-(BB_20-Pad3)") (class "Default")
      (node (ref "BB_20") (pin "3") (pinfunction "3_3") (pintype "passive"))
    )
    (net (code "218") (name "unconnected-(BB_20-Pad4)") (class "Default")
      (node (ref "BB_20") (pin "4") (pinfunction "4_4") (pintype "passive"))
    )
    (net (code "219") (name "unconnected-(BB_20-Pad5)") (class "Default")
      (node (ref "BB_20") (pin "5") (pinfunction "5_5") (pintype "passive"))
    )
    (net (code "220") (name "unconnected-(BB_20-Pad6)") (class "Default")
      (node (ref "BB_20") (pin "6") (pinfunction "6_6") (pintype "passive"))
    )
    (net (code "221") (name "unconnected-(BB_20-Pad7)") (class "Default")
      (node (ref "BB_20") (pin "7") (pinfunction "7_7") (pintype "passive"))
    )
    (net (code "222") (name "unconnected-(BB_20-Pad8)") (class "Default")
      (node (ref "BB_20") (pin "8") (pinfunction "8_8") (pintype "passive"))
    )
    (net (code "223") (name "unconnected-(BB_20-Pad9)") (class "Default")
      (node (ref "BB_20") (pin "9") (pinfunction "9_9") (pintype "passive"))
    )
    (net (code "224") (name "unconnected-(BB_20-Pad10)") (class "Default")
      (node (ref "BB_20") (pin "10") (pinfunction "10_10") (pintype "passive"))
    )
    (net (code "225") (name "unconnected-(BUTTON_1_SYNC-P-Pad3)") (class "Default")
      (node (ref "BUTTON_1_SYNC") (pin "3") (pinfunction "P_3") (pintype "passive"))
    )
    (net (code "226") (name "unconnected-(BUTTON_1_SYNC-S1-Pad2)") (class "Default")
      (node (ref "BUTTON_1_SYNC") (pin "2") (pinfunction "S1_2") (pintype "passive"))
    )
    (net (code "227") (name "unconnected-(BUTTON_2-P-Pad3)") (class "Default")
      (node (ref "BUTTON_2") (pin "3") (pinfunction "P_3") (pintype "passive"))
    )
    (net (code "228") (name "unconnected-(BUTTON_2-S1-Pad2)") (class "Default")
      (node (ref "BUTTON_2") (pin "2") (pinfunction "S1_2") (pintype "passive"))
    )
    (net (code "229") (name "unconnected-(R_ARRAY_1-Pad3)") (class "Default")
      (node (ref "R_ARRAY_1") (pin "3") (pinfunction "3_3") (pintype "passive"))
    )
    (net (code "230") (name "unconnected-(R_ARRAY_1-Pad4)") (class "Default")
      (node (ref "R_ARRAY_1") (pin "4") (pinfunction "4_4") (pintype "passive"))
    )
    (net (code "231") (name "unconnected-(R_ARRAY_1-Pad10)") (class "Default")
      (node (ref "R_ARRAY_1") (pin "10") (pinfunction "10_10") (pintype "passive"))
    )
    (net (code "232") (name "unconnected-(R_ARRAY_2-Pad10)") (class "Default")
      (node (ref "R_ARRAY_2") (pin "10") (pinfunction "10_10") (pintype "passive"))
    )
    (net (code "233") (name "unconnected-(R_ARRAY_2_CON-Pad1)") (class "Default")
      (node (ref "R_ARRAY_2_CON") (pin "1") (pinfunction "1_1") (pintype "passive"))
    )
    (net (code "234") (name "unconnected-(R_ARRAY_2_CON-Pad2)") (class "Default")
      (node (ref "R_ARRAY_2_CON") (pin "2") (pinfunction "2_2") (pintype "passive"))
    )
    (net (code "235") (name "unconnected-(U$1-GND-PadGND@1)") (class "Default")
      (node (ref "U$1") (pin "GND@1") (pinfunction "GND_GND@1") (pintype "bidirectional"))
    )
    (net (code "236") (name "unconnected-(U$1-GND-PadGND@2)") (class "Default")
      (node (ref "U$1") (pin "GND@2") (pinfunction "GND_GND@2") (pintype "bidirectional"))
    )
  )
)
